# LiPo_BMS.net
KiCad netlist of a schematic drawn in Altium Designer
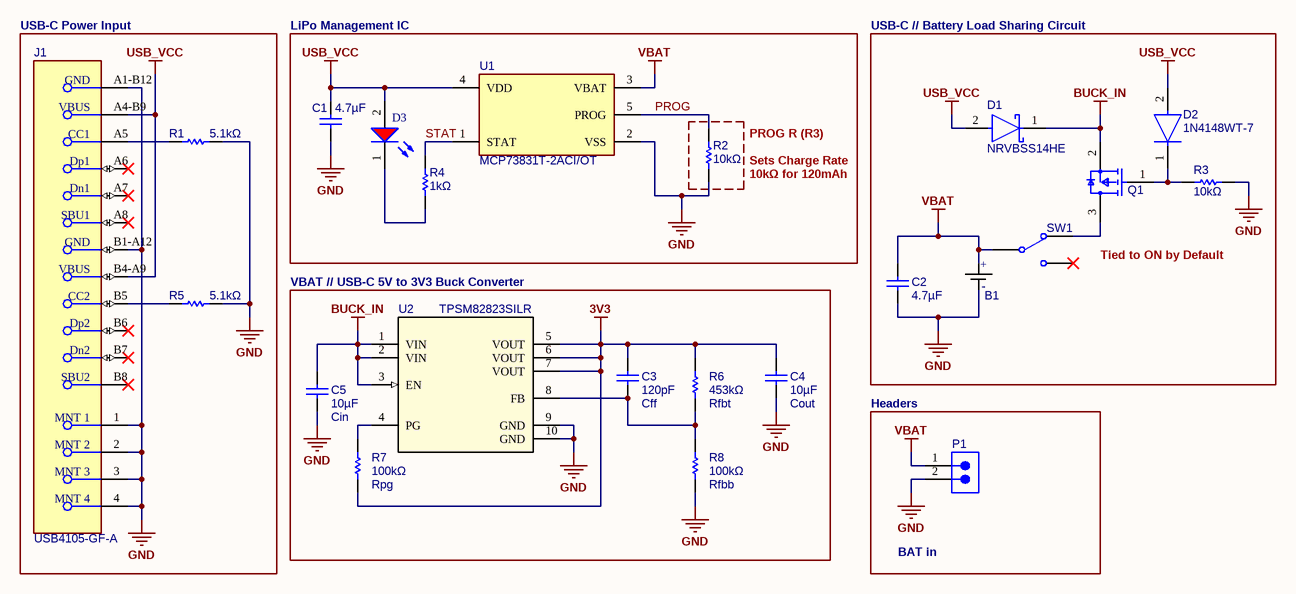
[diagram p0: LiPo BMS.SchDoc]

(export (version "E")
  (design (tool "Eeschema 10.0.6"))
  (components
    (comp (ref "B1") (value "LiPo") (libsource (lib "LiPoSchematicLibrary") (part "3.7V 30mAh LiPo")))
    (comp (ref "C1")
      (value "4.7µF")
      (footprint "WCAP-CSGP_0603_L1.6W0.8H0.8_Reflow")
      (libsource (lib "Altium Content Vault") (part "Capacitor_Non-Polarized"))
    )
    (comp (ref "C2")
      (value "4.7µF")
      (footprint "WCAP-CSGP_0603_L1.6W0.8H0.8_Reflow")
      (libsource (lib "Altium Content Vault") (part "Capacitor_Non-Polarized"))
    )
    (comp (ref "C3")
      (value "120pF")
      (footprint "WCAP-CSGP_0603_L1.6W0.8H0.8_Reflow")
      (libsource (lib "Altium Content Vault") (part "Capacitor_Non-Polarized"))
    )
    (comp (ref "C4")
      (value "10µF")
      (footprint "WCAP-CSGP_0603_L1.6W0.8H0.8_Reflow")
      (description "10V tolerance")
      (libsource (lib "Altium Content Vault") (part "Capacitor_Non-Polarized"))
    )
    (comp (ref "C5")
      (value "10µF")
      (footprint "WCAP-CSGP_0603_L1.6W0.8H0.8_Reflow")
      (libsource (lib "Altium Content Vault") (part "Capacitor_Non-Polarized"))
    )
    (comp (ref "D1")
      (value "NRVBSS14HE")
      (footprint "FP-477AD-MFG")
      (description "NRVBSS14HE Rectifier Diode, Schottky, 1 Phase, 1 Element, 1A, 40V V(RRM), Silicon")
      (libsource (lib "Altium Content Vault") (part "c1678fac7984e62e0809fbf79c06691"))
    )
    (comp (ref "D2")
      (value "1N4148WT-7")
      (footprint "FP-SOD523-MFG")
      (description "DIODE GEN PURP 80V 125MA SOD523")
      (libsource (lib "Altium Content Vault") (part "d7152d700b627762746794eb795d46e"))
    )
    (comp (ref "D3")
      (value "150120RS75000")
      (footprint "WL-SMCW_1206_150120xx75000")
      (description "WL-SMCW SMT Mono-Color Chip LED Waterclear")
      (libsource (lib "Altium Content Vault") (part "LED_Red_2A-1K"))
    )
    (comp (ref "J1")
      (value "USB4105-GF-A")
      (footprint "FP-USB4105-GF-A-MFG")
      (description "CONN RCPT USB2.0 TYPEC 5A")
      (fields
        (field (name "MANUFACTURER") "GCT")
        (field (name "OCTOPART") "https://octopart.com/usb4105-gf-a-gct-106627878")
      )
      (libsource (lib "Altium Content Vault") (part "e7c17a616881a82b79941196b4bec10"))
    )
    (comp (ref "P1")
      (value "61300211121")
      (footprint "61300211121")
      (libsource (lib "Altium Content Vault") (part "Header_Male_1R_02P"))
    )
    (comp (ref "Q1")
      (value "IRLML6402TRPBF")
      (footprint "FP-Micro3-MFG")
      (description "MOSFET P-CH 20V 3.7A SOT-23")
      (fields
        (field (name "OCTOPART") "https://octopart.com/irlml6402trpbf-infineon-65874989")
        (field (name "MANUFACTURER") "Infineon")
      )
      (libsource (lib "Altium Content Vault") (part "566027c8dc92b5207d53ac25ab3eb60"))
    )
    (comp (ref "R1")
      (value "5.1kΩ")
      (footprint "RESC1608X55X25NL10T15")
      (libsource (lib "Altium Content Vault") (part "RES"))
    )
    (comp (ref "R2")
      (value "10kΩ")
      (footprint "RESC1608X55X25NL10T15")
      (libsource (lib "Altium Content Vault") (part "RES"))
    )
    (comp (ref "R3")
      (value "10kΩ")
      (footprint "RESC1608X55X25NL10T15")
      (libsource (lib "Altium Content Vault") (part "RES"))
    )
    (comp (ref "R4")
      (value "1kΩ")
      (footprint "RESC1608X55X25NL10T15")
      (libsource (lib "Altium Content Vault") (part "RES"))
    )
    (comp (ref "R5")
      (value "5.1kΩ")
      (footprint "RESC1608X55X25NL10T15")
      (libsource (lib "Altium Content Vault") (part "RES"))
    )
    (comp (ref "R6")
      (value "453kΩ")
      (footprint "RESC1608X55X25NL10T15")
      (libsource (lib "Altium Content Vault") (part "RES"))
    )
    (comp (ref "R7")
      (value "100kΩ")
      (footprint "RESC1608X55X25NL10T15")
      (libsource (lib "Altium Content Vault") (part "RES"))
    )
    (comp (ref "R8")
      (value "100kΩ")
      (footprint "RESC1608X55X25NL10T15")
      (libsource (lib "Altium Content Vault") (part "RES"))
    )
    (comp (ref "SW1")
      (value "450404015514")
      (footprint "450404015514")
      (description "450404015514 Slide Switch, 0.3A, 5Vdc, Smd Rohs Compliant: Yes")
      (libsource (lib "Altium Content Vault") (part "SPDT"))
    )
    (comp (ref "U1")
      (value "MCP73831T-2ACI/OT")
      (footprint "FP-C04-091-OT-IPC_B")
      (description "IC CONTROLLR LI-ION 4.2V SOT23-5")
      (libsource (lib "Altium Content Vault") (part "61f5a3bb3429d9e0caadea342aa3b19"))
    )
    (comp (ref "U2")
      (value "TPSM82823SILR")
      (footprint "SIL0010D-MFG")
      (description "No Description Available")
      (libsource (lib "TPSM82823SILR") (part "TPSM82823SILR"))
    )
  )
  (nets
    (net (code "1") (name "/PROG") (class "Default")
      (node (ref "R2") (pin "1") (pinfunction "1_1") (pintype "passive"))
      (node (ref "U1") (pin "5") (pinfunction "PROG_5") (pintype "passive"))
    )
    (net (code "2") (name "/STAT") (class "Default")
      (node (ref "R4") (pin "2") (pinfunction "2_2") (pintype "passive"))
      (node (ref "U1") (pin "1") (pinfunction "STAT_1") (pintype "passive"))
    )
    (net (code "3") (name "3V3") (class "Default")
      (node (ref "C3") (pin "2") (pinfunction "2_2") (pintype "passive"))
      (node (ref "C4") (pin "2") (pinfunction "2_2") (pintype "passive"))
      (node (ref "R6") (pin "1") (pinfunction "1_1") (pintype "passive"))
      (node (ref "R7") (pin "2") (pinfunction "2_2") (pintype "passive"))
      (node (ref "U2") (pin "5") (pinfunction "VOUT_5") (pintype "power_in"))
      (node (ref "U2") (pin "6") (pinfunction "VOUT_6") (pintype "power_in"))
      (node (ref "U2") (pin "7") (pinfunction "VOUT_7") (pintype "power_in"))
    )
    (net (code "4") (name "BUCK_IN") (class "Default")
      (node (ref "C5") (pin "2") (pinfunction "2_2") (pintype "passive"))
      (node (ref "D1") (pin "1") (pinfunction "C_1") (pintype "passive"))
      (node (ref "Q1") (pin "2") (pinfunction "S_2") (pintype "passive"))
      (node (ref "U2") (pin "1") (pinfunction "VIN_1") (pintype "power_in"))
      (node (ref "U2") (pin "2") (pinfunction "VIN_2") (pintype "power_in"))
      (node (ref "U2") (pin "3") (pinfunction "EN_3") (pintype "input"))
    )
    (net (code "5") (name "GND") (class "Default")
      (node (ref "B1") (pin "1") (pinfunction "-_1") (pintype "passive"))
      (node (ref "C1") (pin "1") (pinfunction "1_1") (pintype "passive"))
      (node (ref "C2") (pin "1") (pinfunction "1_1") (pintype "passive"))
      (node (ref "C4") (pin "1") (pinfunction "1_1") (pintype "passive"))
      (node (ref "C5") (pin "1") (pinfunction "1_1") (pintype "passive"))
      (node (ref "J1") (pin "1") (pinfunction "MNT_1_1") (pintype "power_in"))
      (node (ref "J1") (pin "2") (pinfunction "MNT_2_2") (pintype "power_in"))
      (node (ref "J1") (pin "3") (pinfunction "MNT_3_3") (pintype "power_in"))
      (node (ref "J1") (pin "4") (pinfunction "MNT_4_4") (pintype "power_in"))
      (node (ref "J1") (pin "A1-B12") (pinfunction "GND_A1-B12") (pintype "power_in"))
      (node (ref "J1") (pin "B1-A12") (pinfunction "GND_B1-A12") (pintype "bidirectional"))
      (node (ref "P1") (pin "2") (pinfunction "2_2") (pintype "passive"))
      (node (ref "R1") (pin "1") (pinfunction "1_1") (pintype "passive"))
      (node (ref "R2") (pin "2") (pinfunction "2_2") (pintype "passive"))
      (node (ref "R3") (pin "2") (pinfunction "2_2") (pintype "passive"))
      (node (ref "R5") (pin "1") (pinfunction "1_1") (pintype "passive"))
      (node (ref "R8") (pin "2") (pinfunction "2_2") (pintype "passive"))
      (node (ref "U1") (pin "2") (pinfunction "VSS_2") (pintype "power_in"))
      (node (ref "U2") (pin "10") (pinfunction "GND_10") (pintype "power_in"))
      (node (ref "U2") (pin "9") (pinfunction "GND_9") (pintype "power_in"))
    )
    (net (code "6") (name "Net-(D2-C)") (class "Default")
      (node (ref "D2") (pin "1") (pinfunction "C_1") (pintype "passive"))
      (node (ref "Q1") (pin "1") (pinfunction "G_1") (pintype "passive"))
      (node (ref "R3") (pin "1") (pinfunction "1_1") (pintype "passive"))
    )
    (net (code "7") (name "Net-(D3-K)") (class "Default")
      (node (ref "D3") (pin "1") (pinfunction "K_1") (pintype "passive"))
      (node (ref "R4") (pin "1") (pinfunction "1_1") (pintype "passive"))
    )
    (net (code "8") (name "Net-(J1-CC1)") (class "Default")
      (node (ref "J1") (pin "A5") (pinfunction "CC1_A5") (pintype "power_in"))
      (node (ref "R1") (pin "2") (pinfunction "2_2") (pintype "passive"))
    )
    (net (code "9") (name "Net-(J1-CC2)") (class "Default")
      (node (ref "J1") (pin "B5") (pinfunction "CC2_B5") (pintype "bidirectional"))
      (node (ref "R5") (pin "2") (pinfunction "2_2") (pintype "passive"))
    )
    (net (code "10") (name "Net-(Q1-D)") (class "Default")
      (node (ref "Q1") (pin "3") (pinfunction "D_3") (pintype "passive"))
      (node (ref "SW1") (pin "L1") (pinfunction "L1_L1") (pintype "passive"))
    )
    (net (code "11") (name "Net-(U2-FB)") (class "Default")
      (node (ref "C3") (pin "1") (pinfunction "1_1") (pintype "passive"))
      (node (ref "R6") (pin "2") (pinfunction "2_2") (pintype "passive"))
      (node (ref "R8") (pin "1") (pinfunction "1_1") (pintype "passive"))
      (node (ref "U2") (pin "8") (pinfunction "FB_8") (pintype "passive"))
    )
    (net (code "12") (name "Net-(U2-PG)") (class "Default")
      (node (ref "R7") (pin "1") (pinfunction "1_1") (pintype "passive"))
      (node (ref "U2") (pin "4") (pinfunction "PG_4") (pintype "open_collector"))
    )
    (net (code "13") (name "USB_VCC") (class "Default")
      (node (ref "C1") (pin "2") (pinfunction "2_2") (pintype "passive"))
      (node (ref "D1") (pin "2") (pinfunction "A_2") (pintype "passive"))
      (node (ref "D2") (pin "2") (pinfunction "A_2") (pintype "passive"))
      (node (ref "D3") (pin "2") (pinfunction "A_2") (pintype "passive"))
      (node (ref "J1") (pin "A4-B9") (pinfunction "VBUS_A4-B9") (pintype "power_in"))
      (node (ref "J1") (pin "B4-A9") (pinfunction "VBUS_B4-A9") (pintype "bidirectional"))
      (node (ref "U1") (pin "4") (pinfunction "VDD_4") (pintype "power_in"))
    )
    (net (code "14") (name "VBAT") (class "Default")
      (node (ref "B1") (pin "0") (pinfunction "+_0") (pintype "passive"))
      (node (ref "C2") (pin "2") (pinfunction "2_2") (pintype "passive"))
      (node (ref "P1") (pin "1") (pinfunction "1_1") (pintype "passive"))
      (node (ref "SW1") (pin "COM") (pinfunction "COM_COM") (pintype "passive"))
      (node (ref "U1") (pin "3") (pinfunction "VBAT_3") (pintype "power_in"))
    )
    (net (code "15") (name "unconnected-(J1-Dn1-PadA7)") (class "Default")
      (node (ref "J1") (pin "A7") (pinfunction "Dn1_A7") (pintype "bidirectional+no_connect"))
    )
    (net (code "16") (name "unconnected-(J1-Dn2-PadB7)") (class "Default")
      (node (ref "J1") (pin "B7") (pinfunction "Dn2_B7") (pintype "bidirectional+no_connect"))
    )
    (net (code "17") (name "unconnected-(J1-Dp1-PadA6)") (class "Default")
      (node (ref "J1") (pin "A6") (pinfunction "Dp1_A6") (pintype "bidirectional+no_connect"))
    )
    (net (code "18") (name "unconnected-(J1-Dp2-PadB6)") (class "Default")
      (node (ref "J1") (pin "B6") (pinfunction "Dp2_B6") (pintype "bidirectional+no_connect"))
    )
    (net (code "19") (name "unconnected-(J1-SBU1-PadA8)") (class "Default")
      (node (ref "J1") (pin "A8") (pinfunction "SBU1_A8") (pintype "bidirectional+no_connect"))
    )
    (net (code "20") (name "unconnected-(J1-SBU2-PadB8)") (class "Default")
      (node (ref "J1") (pin "B8") (pinfunction "SBU2_B8") (pintype "power_in+no_connect"))
    )
    (net (code "21") (name "unconnected-(SW1-PadL2)") (class "Default")
      (node (ref "SW1") (pin "L2") (pinfunction "L2_L2") (pintype "passive+no_connect"))
    )
  )
)
